# SL_FPGA_Auto_2E.net
KiCad netlist of a schematic drawn in Altium Designer
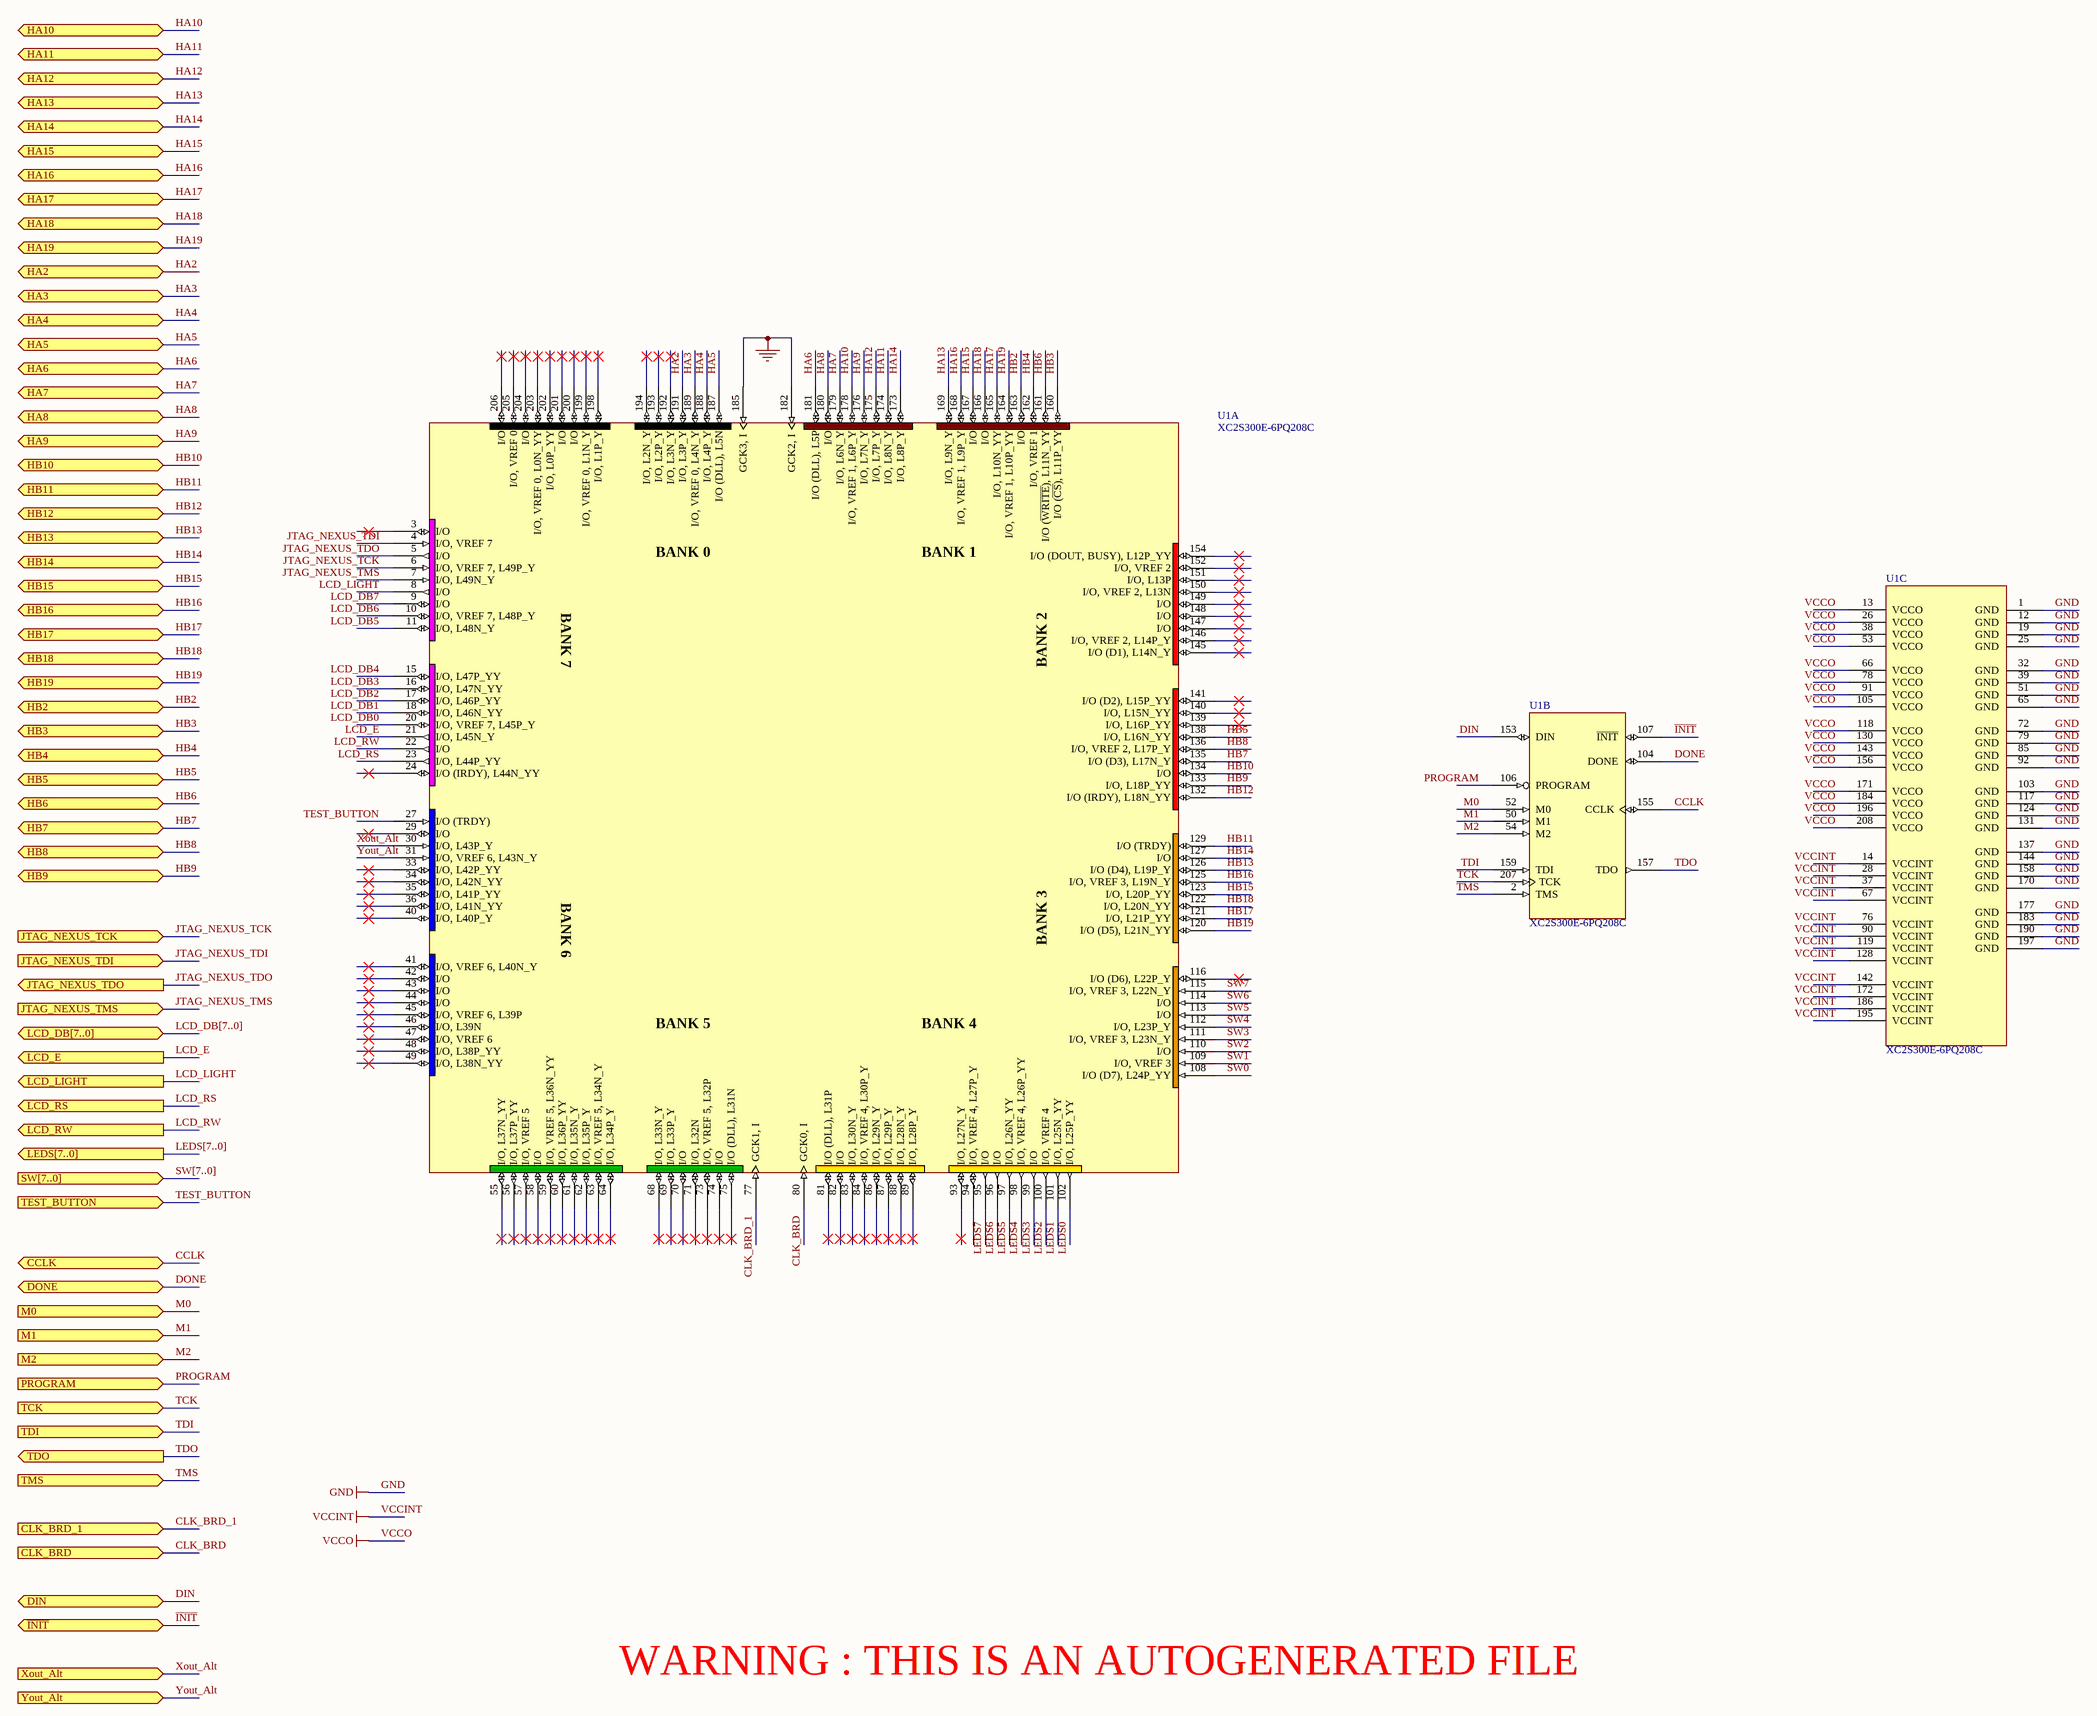
[diagram p0: SL_FPGA_Auto_2E.SchDoc]

(export (version "E")
  (design (tool "Eeschema 10.0.6"))
  (components
    (comp (ref "U1")
      (value "XC2S300E-6PQ208C")
      (footprint "PQ208")
      (description "Spartan-IIE 1.8V FPGA, 208-Pin PQFP, Standard Performance, Commercial Grade")
      (fields (field (name "PUBLISHER") "Altium Limited"))
      (libsource (lib "*") (part "XC2S300E-6PQ208C"))
    )
  )
  (nets
    (net (code "1") (name "/CCLK") (class "Default")
      (node (ref "U1") (pin "155") (pinfunction "CCLK_155") (pintype "bidirectional"))
    )
    (net (code "2") (name "/CLK_BRD") (class "Default")
      (node (ref "U1") (pin "80") (pinfunction "GCK0,_I_80") (pintype "input"))
    )
    (net (code "3") (name "/CLK_BRD_1") (class "Default")
      (node (ref "U1") (pin "77") (pinfunction "GCK1,_I_77") (pintype "input"))
    )
    (net (code "4") (name "/DIN") (class "Default")
      (node (ref "U1") (pin "153") (pinfunction "DIN_153") (pintype "bidirectional"))
    )
    (net (code "5") (name "/DONE") (class "Default")
      (node (ref "U1") (pin "104") (pinfunction "DONE_104") (pintype "bidirectional"))
    )
    (net (code "6") (name "/HA2") (class "Default")
      (node (ref "U1") (pin "191") (pinfunction "I/O,_L3P_Y_191") (pintype "bidirectional"))
    )
    (net (code "7") (name "/HA3") (class "Default")
      (node (ref "U1") (pin "189") (pinfunction "I/O,_VREF_0,_L4N_Y_189") (pintype "bidirectional"))
    )
    (net (code "8") (name "/HA4") (class "Default")
      (node (ref "U1") (pin "188") (pinfunction "I/O,_L4P_Y_188") (pintype "bidirectional"))
    )
    (net (code "9") (name "/HA5") (class "Default")
      (node (ref "U1") (pin "187") (pinfunction "I/O_(DLL),_L5N_187") (pintype "bidirectional"))
    )
    (net (code "10") (name "/HA6") (class "Default")
      (node (ref "U1") (pin "181") (pinfunction "I/O_(DLL),_L5P_181") (pintype "bidirectional"))
    )
    (net (code "11") (name "/HA7") (class "Default")
      (node (ref "U1") (pin "179") (pinfunction "I/O,_L6N_Y_179") (pintype "bidirectional"))
    )
    (net (code "12") (name "/HA8") (class "Default")
      (node (ref "U1") (pin "180") (pinfunction "I/O_180") (pintype "bidirectional"))
    )
    (net (code "13") (name "/HA9") (class "Default")
      (node (ref "U1") (pin "176") (pinfunction "I/O,_L7N_Y_176") (pintype "bidirectional"))
    )
    (net (code "14") (name "/HA10") (class "Default")
      (node (ref "U1") (pin "178") (pinfunction "I/O,_VREF_1,_L6P_Y_178") (pintype "bidirectional"))
    )
    (net (code "15") (name "/HA11") (class "Default")
      (node (ref "U1") (pin "174") (pinfunction "I/O,_L8N_Y_174") (pintype "bidirectional"))
    )
    (net (code "16") (name "/HA12") (class "Default")
      (node (ref "U1") (pin "175") (pinfunction "I/O,_L7P_Y_175") (pintype "bidirectional"))
    )
    (net (code "17") (name "/HA13") (class "Default")
      (node (ref "U1") (pin "169") (pinfunction "I/O,_L9N_Y_169") (pintype "bidirectional"))
    )
    (net (code "18") (name "/HA14") (class "Default")
      (node (ref "U1") (pin "173") (pinfunction "I/O,_L8P_Y_173") (pintype "bidirectional"))
    )
    (net (code "19") (name "/HA15") (class "Default")
      (node (ref "U1") (pin "167") (pinfunction "I/O_167") (pintype "bidirectional"))
    )
    (net (code "20") (name "/HA16") (class "Default")
      (node (ref "U1") (pin "168") (pinfunction "I/O,_VREF_1,_L9P_Y_168") (pintype "bidirectional"))
    )
    (net (code "21") (name "/HA17") (class "Default")
      (node (ref "U1") (pin "165") (pinfunction "I/O,_L10N_YY_165") (pintype "bidirectional"))
    )
    (net (code "22") (name "/HA18") (class "Default")
      (node (ref "U1") (pin "166") (pinfunction "I/O_166") (pintype "bidirectional"))
    )
    (net (code "23") (name "/HA19") (class "Default")
      (node (ref "U1") (pin "164") (pinfunction "I/O,_VREF_1,_L10P_YY_164") (pintype "bidirectional"))
    )
    (net (code "24") (name "/HB2") (class "Default")
      (node (ref "U1") (pin "163") (pinfunction "I/O_163") (pintype "bidirectional"))
    )
    (net (code "25") (name "/HB3") (class "Default")
      (node (ref "U1") (pin "160") (pinfunction "I/O_(~{CS}),_L11P_YY_160") (pintype "bidirectional"))
    )
    (net (code "26") (name "/HB4") (class "Default")
      (node (ref "U1") (pin "162") (pinfunction "I/O,_VREF_1_162") (pintype "bidirectional"))
    )
    (net (code "27") (name "/HB5") (class "Default")
      (node (ref "U1") (pin "138") (pinfunction "I/O,_L16N_YY_138") (pintype "bidirectional"))
    )
    (net (code "28") (name "/HB6") (class "Default")
      (node (ref "U1") (pin "161") (pinfunction "I/O_(~{WRITE}),_L11N_YY_161") (pintype "bidirectional"))
    )
    (net (code "29") (name "/HB7") (class "Default")
      (node (ref "U1") (pin "135") (pinfunction "I/O_(D3),_L17N_Y_135") (pintype "bidirectional"))
    )
    (net (code "30") (name "/HB8") (class "Default")
      (node (ref "U1") (pin "136") (pinfunction "I/O,_VREF_2,_L17P_Y_136") (pintype "bidirectional"))
    )
    (net (code "31") (name "/HB9") (class "Default")
      (node (ref "U1") (pin "133") (pinfunction "I/O,_L18P_YY_133") (pintype "bidirectional"))
    )
    (net (code "32") (name "/HB10") (class "Default")
      (node (ref "U1") (pin "134") (pinfunction "I/O_134") (pintype "bidirectional"))
    )
    (net (code "33") (name "/HB11") (class "Default")
      (node (ref "U1") (pin "129") (pinfunction "I/O_(TRDY)_129") (pintype "bidirectional"))
    )
    (net (code "34") (name "/HB12") (class "Default")
      (node (ref "U1") (pin "132") (pinfunction "I/O_(IRDY),_L18N_YY_132") (pintype "bidirectional"))
    )
    (net (code "35") (name "/HB13") (class "Default")
      (node (ref "U1") (pin "126") (pinfunction "I/O_(D4),_L19P_Y_126") (pintype "bidirectional"))
    )
    (net (code "36") (name "/HB14") (class "Default")
      (node (ref "U1") (pin "127") (pinfunction "I/O_127") (pintype "bidirectional"))
    )
    (net (code "37") (name "/HB15") (class "Default")
      (node (ref "U1") (pin "123") (pinfunction "I/O,_L20P_YY_123") (pintype "bidirectional"))
    )
    (net (code "38") (name "/HB16") (class "Default")
      (node (ref "U1") (pin "125") (pinfunction "I/O,_VREF_3,_L19N_Y_125") (pintype "bidirectional"))
    )
    (net (code "39") (name "/HB17") (class "Default")
      (node (ref "U1") (pin "121") (pinfunction "I/O,_L21P_YY_121") (pintype "bidirectional"))
    )
    (net (code "40") (name "/HB18") (class "Default")
      (node (ref "U1") (pin "122") (pinfunction "I/O,_L20N_YY_122") (pintype "bidirectional"))
    )
    (net (code "41") (name "/HB19") (class "Default")
      (node (ref "U1") (pin "120") (pinfunction "I/O_(D5),_L21N_YY_120") (pintype "bidirectional"))
    )
    (net (code "42") (name "/JTAG_NEXUS_TCK") (class "Default")
      (node (ref "U1") (pin "6") (pinfunction "I/O,_VREF_7,_L49P_Y_6") (pintype "input"))
    )
    (net (code "43") (name "/JTAG_NEXUS_TDI") (class "Default")
      (node (ref "U1") (pin "4") (pinfunction "I/O,_VREF_7_4") (pintype "input"))
    )
    (net (code "44") (name "/JTAG_NEXUS_TDO") (class "Default")
      (node (ref "U1") (pin "5") (pinfunction "I/O_5") (pintype "output"))
    )
    (net (code "45") (name "/JTAG_NEXUS_TMS") (class "Default")
      (node (ref "U1") (pin "7") (pinfunction "I/O,_L49N_Y_7") (pintype "input"))
    )
    (net (code "46") (name "/LCD_DB0") (class "Default")
      (node (ref "U1") (pin "20") (pinfunction "I/O,_VREF_7,_L45P_Y_20") (pintype "bidirectional"))
    )
    (net (code "47") (name "/LCD_DB1") (class "Default")
      (node (ref "U1") (pin "18") (pinfunction "I/O,_L46N_YY_18") (pintype "bidirectional"))
    )
    (net (code "48") (name "/LCD_DB2") (class "Default")
      (node (ref "U1") (pin "17") (pinfunction "I/O,_L46P_YY_17") (pintype "bidirectional"))
    )
    (net (code "49") (name "/LCD_DB3") (class "Default")
      (node (ref "U1") (pin "16") (pinfunction "I/O,_L47N_YY_16") (pintype "bidirectional"))
    )
    (net (code "50") (name "/LCD_DB4") (class "Default")
      (node (ref "U1") (pin "15") (pinfunction "I/O,_L47P_YY_15") (pintype "bidirectional"))
    )
    (net (code "51") (name "/LCD_DB5") (class "Default")
      (node (ref "U1") (pin "11") (pinfunction "I/O,_L48N_Y_11") (pintype "bidirectional"))
    )
    (net (code "52") (name "/LCD_DB6") (class "Default")
      (node (ref "U1") (pin "10") (pinfunction "I/O,_VREF_7,_L48P_Y_10") (pintype "bidirectional"))
    )
    (net (code "53") (name "/LCD_DB7") (class "Default")
      (node (ref "U1") (pin "9") (pinfunction "I/O_9") (pintype "bidirectional"))
    )
    (net (code "55") (name "/LCD_E") (class "Default")
      (node (ref "U1") (pin "21") (pinfunction "I/O,_L45N_Y_21") (pintype "output"))
    )
    (net (code "56") (name "/LCD_LIGHT") (class "Default")
      (node (ref "U1") (pin "8") (pinfunction "I/O_8") (pintype "output"))
    )
    (net (code "57") (name "/LCD_RS") (class "Default")
      (node (ref "U1") (pin "23") (pinfunction "I/O,_L44P_YY_23") (pintype "output"))
    )
    (net (code "58") (name "/LCD_RW") (class "Default")
      (node (ref "U1") (pin "22") (pinfunction "I/O_22") (pintype "output"))
    )
    (net (code "59") (name "/LEDS0") (class "Default")
      (node (ref "U1") (pin "102") (pinfunction "I/O,_L25P_YY_102") (pintype "output"))
    )
    (net (code "60") (name "/LEDS1") (class "Default")
      (node (ref "U1") (pin "101") (pinfunction "I/O,_L25N_YY_101") (pintype "output"))
    )
    (net (code "61") (name "/LEDS2") (class "Default")
      (node (ref "U1") (pin "100") (pinfunction "I/O,_VREF_4_100") (pintype "output"))
    )
    (net (code "62") (name "/LEDS3") (class "Default")
      (node (ref "U1") (pin "99") (pinfunction "I/O_99") (pintype "output"))
    )
    (net (code "63") (name "/LEDS4") (class "Default")
      (node (ref "U1") (pin "98") (pinfunction "I/O,_VREF_4,_L26P_YY_98") (pintype "output"))
    )
    (net (code "64") (name "/LEDS5") (class "Default")
      (node (ref "U1") (pin "97") (pinfunction "I/O,_L26N_YY_97") (pintype "output"))
    )
    (net (code "65") (name "/LEDS6") (class "Default")
      (node (ref "U1") (pin "96") (pinfunction "I/O_96") (pintype "output"))
    )
    (net (code "66") (name "/LEDS7") (class "Default")
      (node (ref "U1") (pin "95") (pinfunction "I/O_95") (pintype "output"))
    )
    (net (code "68") (name "/M0") (class "Default")
      (node (ref "U1") (pin "52") (pinfunction "M0_52") (pintype "input"))
    )
    (net (code "69") (name "/M1") (class "Default")
      (node (ref "U1") (pin "50") (pinfunction "M1_50") (pintype "input"))
    )
    (net (code "70") (name "/M2") (class "Default")
      (node (ref "U1") (pin "54") (pinfunction "M2_54") (pintype "input"))
    )
    (net (code "71") (name "/PROGRAM") (class "Default")
      (node (ref "U1") (pin "106") (pinfunction "PROGRAM_106") (pintype "input"))
    )
    (net (code "72") (name "/SW0") (class "Default")
      (node (ref "U1") (pin "108") (pinfunction "I/O_(D7),_L24P_YY_108") (pintype "input"))
    )
    (net (code "73") (name "/SW1") (class "Default")
      (node (ref "U1") (pin "109") (pinfunction "I/O,_VREF_3_109") (pintype "input"))
    )
    (net (code "74") (name "/SW2") (class "Default")
      (node (ref "U1") (pin "110") (pinfunction "I/O_110") (pintype "input"))
    )
    (net (code "75") (name "/SW3") (class "Default")
      (node (ref "U1") (pin "111") (pinfunction "I/O,_VREF_3,_L23N_Y_111") (pintype "input"))
    )
    (net (code "76") (name "/SW4") (class "Default")
      (node (ref "U1") (pin "112") (pinfunction "I/O,_L23P_Y_112") (pintype "input"))
    )
    (net (code "77") (name "/SW5") (class "Default")
      (node (ref "U1") (pin "113") (pinfunction "I/O_113") (pintype "input"))
    )
    (net (code "78") (name "/SW6") (class "Default")
      (node (ref "U1") (pin "114") (pinfunction "I/O_114") (pintype "input"))
    )
    (net (code "79") (name "/SW7") (class "Default")
      (node (ref "U1") (pin "115") (pinfunction "I/O,_VREF_3,_L22N_Y_115") (pintype "input"))
    )
    (net (code "81") (name "/TCK") (class "Default")
      (node (ref "U1") (pin "207") (pinfunction "TCK_207") (pintype "input"))
    )
    (net (code "82") (name "/TDI") (class "Default")
      (node (ref "U1") (pin "159") (pinfunction "TDI_159") (pintype "input"))
    )
    (net (code "83") (name "/TDO") (class "Default")
      (node (ref "U1") (pin "157") (pinfunction "TDO_157") (pintype "output"))
    )
    (net (code "84") (name "/TEST_BUTTON") (class "Default")
      (node (ref "U1") (pin "27") (pinfunction "I/O_(TRDY)_27") (pintype "input"))
    )
    (net (code "85") (name "/TMS") (class "Default")
      (node (ref "U1") (pin "2") (pinfunction "TMS_2") (pintype "input"))
    )
    (net (code "86") (name "/Xout_Alt") (class "Default")
      (node (ref "U1") (pin "30") (pinfunction "I/O,_L43P_Y_30") (pintype "input"))
    )
    (net (code "87") (name "/Yout_Alt") (class "Default")
      (node (ref "U1") (pin "31") (pinfunction "I/O,_VREF_6,_L43N_Y_31") (pintype "input"))
    )
    (net (code "88") (name "/~{INIT}") (class "Default")
      (node (ref "U1") (pin "107") (pinfunction "~{INIT}_107") (pintype "bidirectional"))
    )
    (net (code "89") (name "GND") (class "Default")
      (node (ref "U1") (pin "1") (pinfunction "GND_1") (pintype "power_in"))
      (node (ref "U1") (pin "103") (pinfunction "GND_103") (pintype "power_in"))
      (node (ref "U1") (pin "117") (pinfunction "GND_117") (pintype "power_in"))
      (node (ref "U1") (pin "12") (pinfunction "GND_12") (pintype "power_in"))
      (node (ref "U1") (pin "124") (pinfunction "GND_124") (pintype "power_in"))
      (node (ref "U1") (pin "131") (pinfunction "GND_131") (pintype "power_in"))
      (node (ref "U1") (pin "137") (pinfunction "GND_137") (pintype "power_in"))
      (node (ref "U1") (pin "144") (pinfunction "GND_144") (pintype "power_in"))
      (node (ref "U1") (pin "158") (pinfunction "GND_158") (pintype "power_in"))
      (node (ref "U1") (pin "170") (pinfunction "GND_170") (pintype "power_in"))
      (node (ref "U1") (pin "177") (pinfunction "GND_177") (pintype "power_in"))
      (node (ref "U1") (pin "182") (pinfunction "GCK2,_I_182") (pintype "input"))
      (node (ref "U1") (pin "183") (pinfunction "GND_183") (pintype "power_in"))
      (node (ref "U1") (pin "185") (pinfunction "GCK3,_I_185") (pintype "input"))
      (node (ref "U1") (pin "19") (pinfunction "GND_19") (pintype "power_in"))
      (node (ref "U1") (pin "190") (pinfunction "GND_190") (pintype "power_in"))
      (node (ref "U1") (pin "197") (pinfunction "GND_197") (pintype "power_in"))
      (node (ref "U1") (pin "25") (pinfunction "GND_25") (pintype "power_in"))
      (node (ref "U1") (pin "32") (pinfunction "GND_32") (pintype "power_in"))
      (node (ref "U1") (pin "39") (pinfunction "GND_39") (pintype "power_in"))
      (node (ref "U1") (pin "51") (pinfunction "GND_51") (pintype "power_in"))
      (node (ref "U1") (pin "65") (pinfunction "GND_65") (pintype "power_in"))
      (node (ref "U1") (pin "72") (pinfunction "GND_72") (pintype "power_in"))
      (node (ref "U1") (pin "79") (pinfunction "GND_79") (pintype "power_in"))
      (node (ref "U1") (pin "85") (pinfunction "GND_85") (pintype "power_in"))
      (node (ref "U1") (pin "92") (pinfunction "GND_92") (pintype "power_in"))
    )
    (net (code "90") (name "VCCINT") (class "Default")
      (node (ref "U1") (pin "119") (pinfunction "VCCINT_119") (pintype "power_in"))
      (node (ref "U1") (pin "128") (pinfunction "VCCINT_128") (pintype "power_in"))
      (node (ref "U1") (pin "14") (pinfunction "VCCINT_14") (pintype "power_in"))
      (node (ref "U1") (pin "142") (pinfunction "VCCINT_142") (pintype "power_in"))
      (node (ref "U1") (pin "172") (pinfunction "VCCINT_172") (pintype "power_in"))
      (node (ref "U1") (pin "186") (pinfunction "VCCINT_186") (pintype "power_in"))
      (node (ref "U1") (pin "195") (pinfunction "VCCINT_195") (pintype "power_in"))
      (node (ref "U1") (pin "28") (pinfunction "VCCINT_28") (pintype "power_in"))
      (node (ref "U1") (pin "37") (pinfunction "VCCINT_37") (pintype "power_in"))
      (node (ref "U1") (pin "67") (pinfunction "VCCINT_67") (pintype "power_in"))
      (node (ref "U1") (pin "76") (pinfunction "VCCINT_76") (pintype "power_in"))
      (node (ref "U1") (pin "90") (pinfunction "VCCINT_90") (pintype "power_in"))
    )
    (net (code "91") (name "VCCO") (class "Default")
      (node (ref "U1") (pin "105") (pinfunction "VCCO_105") (pintype "power_in"))
      (node (ref "U1") (pin "118") (pinfunction "VCCO_118") (pintype "power_in"))
      (node (ref "U1") (pin "13") (pinfunction "VCCO_13") (pintype "power_in"))
      (node (ref "U1") (pin "130") (pinfunction "VCCO_130") (pintype "power_in"))
      (node (ref "U1") (pin "143") (pinfunction "VCCO_143") (pintype "power_in"))
      (node (ref "U1") (pin "156") (pinfunction "VCCO_156") (pintype "power_in"))
      (node (ref "U1") (pin "171") (pinfunction "VCCO_171") (pintype "power_in"))
      (node (ref "U1") (pin "184") (pinfunction "VCCO_184") (pintype "power_in"))
      (node (ref "U1") (pin "196") (pinfunction "VCCO_196") (pintype "power_in"))
      (node (ref "U1") (pin "208") (pinfunction "VCCO_208") (pintype "power_in"))
      (node (ref "U1") (pin "26") (pinfunction "VCCO_26") (pintype "power_in"))
      (node (ref "U1") (pin "38") (pinfunction "VCCO_38") (pintype "power_in"))
      (node (ref "U1") (pin "53") (pinfunction "VCCO_53") (pintype "power_in"))
      (node (ref "U1") (pin "66") (pinfunction "VCCO_66") (pintype "power_in"))
      (node (ref "U1") (pin "78") (pinfunction "VCCO_78") (pintype "power_in"))
      (node (ref "U1") (pin "91") (pinfunction "VCCO_91") (pintype "power_in"))
    )
    (net (code "92") (name "unconnected-(U1A-I{slash}O,_L0P_YY-Pad202)") (class "Default")
      (node (ref "U1") (pin "202") (pinfunction "I/O,_L0P_YY_202") (pintype "bidirectional"))
    )
    (net (code "93") (name "unconnected-(U1A-I{slash}O,_L1P_Y-Pad198)") (class "Default")
      (node (ref "U1") (pin "198") (pinfunction "I/O,_L1P_Y_198") (pintype "bidirectional"))
    )
    (net (code "94") (name "unconnected-(U1A-I{slash}O,_L2N_Y-Pad194)") (class "Default")
      (node (ref "U1") (pin "194") (pinfunction "I/O,_L2N_Y_194") (pintype "bidirectional"))
    )
    (net (code "95") (name "unconnected-(U1A-I{slash}O,_L2P_Y-Pad193)") (class "Default")
      (node (ref "U1") (pin "193") (pinfunction "I/O,_L2P_Y_193") (pintype "bidirectional"))
    )
    (net (code "96") (name "unconnected-(U1A-I{slash}O,_L3N_Y-Pad192)") (class "Default")
      (node (ref "U1") (pin "192") (pinfunction "I/O,_L3N_Y_192") (pintype "bidirectional"))
    )
    (net (code "97") (name "unconnected-(U1A-I{slash}O,_L13P-Pad151)") (class "Default")
      (node (ref "U1") (pin "151") (pinfunction "I/O,_L13P_151") (pintype "bidirectional"))
    )
    (net (code "98") (name "unconnected-(U1A-I{slash}O,_L15N_YY-Pad140)") (class "Default")
      (node (ref "U1") (pin "140") (pinfunction "I/O,_L15N_YY_140") (pintype "bidirectional"))
    )
    (net (code "99") (name "unconnected-(U1A-I{slash}O,_L16P_YY-Pad139)") (class "Default")
      (node (ref "U1") (pin "139") (pinfunction "I/O,_L16P_YY_139") (pintype "bidirectional"))
    )
    (net (code "100") (name "unconnected-(U1A-I{slash}O,_L27N_Y-Pad93)") (class "Default")
      (node (ref "U1") (pin "93") (pinfunction "I/O,_L27N_Y_93") (pintype "bidirectional"))
    )
    (net (code "101") (name "unconnected-(U1A-I{slash}O,_L28N_Y-Pad88)") (class "Default")
      (node (ref "U1") (pin "88") (pinfunction "I/O,_L28N_Y_88") (pintype "bidirectional"))
    )
    (net (code "102") (name "unconnected-(U1A-I{slash}O,_L28P_Y-Pad89)") (class "Default")
      (node (ref "U1") (pin "89") (pinfunction "I/O,_L28P_Y_89") (pintype "bidirectional"))
    )
    (net (code "103") (name "unconnected-(U1A-I{slash}O,_L29N_Y-Pad86)") (class "Default")
      (node (ref "U1") (pin "86") (pinfunction "I/O,_L29N_Y_86") (pintype "bidirectional"))
    )
    (net (code "104") (name "unconnected-(U1A-I{slash}O,_L29P_Y-Pad87)") (class "Default")
      (node (ref "U1") (pin "87") (pinfunction "I/O,_L29P_Y_87") (pintype "bidirectional"))
    )
    (net (code "105") (name "unconnected-(U1A-I{slash}O,_L30N_Y-Pad83)") (class "Default")
      (node (ref "U1") (pin "83") (pinfunction "I/O,_L30N_Y_83") (pintype "bidirectional"))
    )
    (net (code "106") (name "unconnected-(U1A-I{slash}O,_L32N-Pad71)") (class "Default")
      (node (ref "U1") (pin "71") (pinfunction "I/O,_L32N_71") (pintype "bidirectional"))
    )
    (net (code "107") (name "unconnected-(U1A-I{slash}O,_L33N_Y-Pad68)") (class "Default")
      (node (ref "U1") (pin "68") (pinfunction "I/O,_L33N_Y_68") (pintype "bidirectional"))
    )
    (net (code "108") (name "unconnected-(U1A-I{slash}O,_L33P_Y-Pad69)") (class "Default")
      (node (ref "U1") (pin "69") (pinfunction "I/O,_L33P_Y_69") (pintype "bidirectional"))
    )
    (net (code "109") (name "unconnected-(U1A-I{slash}O,_L34P_Y-Pad64)") (class "Default")
      (node (ref "U1") (pin "64") (pinfunction "I/O,_L34P_Y_64") (pintype "bidirectional"))
    )
    (net (code "110") (name "unconnected-(U1A-I{slash}O,_L35N_Y-Pad61)") (class "Default")
      (node (ref "U1") (pin "61") (pinfunction "I/O,_L35N_Y_61") (pintype "bidirectional"))
    )
    (net (code "111") (name "unconnected-(U1A-I{slash}O,_L35P_Y-Pad62)") (class "Default")
      (node (ref "U1") (pin "62") (pinfunction "I/O,_L35P_Y_62") (pintype "bidirectional"))
    )
    (net (code "112") (name "unconnected-(U1A-I{slash}O,_L36P_YY-Pad60)") (class "Default")
      (node (ref "U1") (pin "60") (pinfunction "I/O,_L36P_YY_60") (pintype "bidirectional"))
    )
    (net (code "113") (name "unconnected-(U1A-I{slash}O,_L37N_YY-Pad55)") (class "Default")
      (node (ref "U1") (pin "55") (pinfunction "I/O,_L37N_YY_55") (pintype "bidirectional"))
    )
    (net (code "114") (name "unconnected-(U1A-I{slash}O,_L37P_YY-Pad56)") (class "Default")
      (node (ref "U1") (pin "56") (pinfunction "I/O,_L37P_YY_56") (pintype "bidirectional"))
    )
    (net (code "115") (name "unconnected-(U1A-I{slash}O,_L38N_YY-Pad49)") (class "Default")
      (node (ref "U1") (pin "49") (pinfunction "I/O,_L38N_YY_49") (pintype "bidirectional"))
    )
    (net (code "116") (name "unconnected-(U1A-I{slash}O,_L38P_YY-Pad48)") (class "Default")
      (node (ref "U1") (pin "48") (pinfunction "I/O,_L38P_YY_48") (pintype "bidirectional"))
    )
    (net (code "117") (name "unconnected-(U1A-I{slash}O,_L39N-Pad46)") (class "Default")
      (node (ref "U1") (pin "46") (pinfunction "I/O,_L39N_46") (pintype "bidirectional"))
    )
    (net (code "118") (name "unconnected-(U1A-I{slash}O,_L40P_Y-Pad40)") (class "Default")
      (node (ref "U1") (pin "40") (pinfunction "I/O,_L40P_Y_40") (pintype "bidirectional"))
    )
    (net (code "119") (name "unconnected-(U1A-I{slash}O,_L41N_YY-Pad36)") (class "Default")
      (node (ref "U1") (pin "36") (pinfunction "I/O,_L41N_YY_36") (pintype "bidirectional"))
    )
    (net (code "120") (name "unconnected-(U1A-I{slash}O,_L41P_YY-Pad35)") (class "Default")
      (node (ref "U1") (pin "35") (pinfunction "I/O,_L41P_YY_35") (pintype "bidirectional"))
    )
    (net (code "121") (name "unconnected-(U1A-I{slash}O,_L42N_YY-Pad34)") (class "Default")
      (node (ref "U1") (pin "34") (pinfunction "I/O,_L42N_YY_34") (pintype "bidirectional"))
    )
    (net (code "122") (name "unconnected-(U1A-I{slash}O,_L42P_YY-Pad33)") (class "Default")
      (node (ref "U1") (pin "33") (pinfunction "I/O,_L42P_YY_33") (pintype "bidirectional"))
    )
    (net (code "123") (name "unconnected-(U1A-I{slash}O,_VREF_0,_L0N_YY-Pad203)") (class "Default")
      (node (ref "U1") (pin "203") (pinfunction "I/O,_VREF_0,_L0N_YY_203") (pintype "bidirectional"))
    )
    (net (code "124") (name "unconnected-(U1A-I{slash}O,_VREF_0,_L1N_Y-Pad199)") (class "Default")
      (node (ref "U1") (pin "199") (pinfunction "I/O,_VREF_0,_L1N_Y_199") (pintype "bidirectional"))
    )
    (net (code "125") (name "unconnected-(U1A-I{slash}O,_VREF_0-Pad205)") (class "Default")
      (node (ref "U1") (pin "205") (pinfunction "I/O,_VREF_0_205") (pintype "bidirectional"))
    )
    (net (code "126") (name "unconnected-(U1A-I{slash}O,_VREF_2,_L13N-Pad150)") (class "Default")
      (node (ref "U1") (pin "150") (pinfunction "I/O,_VREF_2,_L13N_150") (pintype "bidirectional"))
    )
    (net (code "127") (name "unconnected-(U1A-I{slash}O,_VREF_2,_L14P_Y-Pad146)") (class "Default")
      (node (ref "U1") (pin "146") (pinfunction "I/O,_VREF_2,_L14P_Y_146") (pintype "bidirectional"))
    )
    (net (code "128") (name "unconnected-(U1A-I{slash}O,_VREF_2-Pad152)") (class "Default")
      (node (ref "U1") (pin "152") (pinfunction "I/O,_VREF_2_152") (pintype "bidirectional"))
    )
    (net (code "129") (name "unconnected-(U1A-I{slash}O,_VREF_4,_L27P_Y-Pad94)") (class "Default")
      (node (ref "U1") (pin "94") (pinfunction "I/O,_VREF_4,_L27P_Y_94") (pintype "bidirectional"))
    )
    (net (code "130") (name "unconnected-(U1A-I{slash}O,_VREF_4,_L30P_Y-Pad84)") (class "Default")
      (node (ref "U1") (pin "84") (pinfunction "I/O,_VREF_4,_L30P_Y_84") (pintype "bidirectional"))
    )
    (net (code "131") (name "unconnected-(U1A-I{slash}O,_VREF_5,_L32P-Pad73)") (class "Default")
      (node (ref "U1") (pin "73") (pinfunction "I/O,_VREF_5,_L32P_73") (pintype "bidirectional"))
    )
    (net (code "132") (name "unconnected-(U1A-I{slash}O,_VREF_5,_L34N_Y-Pad63)") (class "Default")
      (node (ref "U1") (pin "63") (pinfunction "I/O,_VREF_5,_L34N_Y_63") (pintype "bidirectional"))
    )
    (net (code "133") (name "unconnected-(U1A-I{slash}O,_VREF_5,_L36N_YY-Pad59)") (class "Default")
      (node (ref "U1") (pin "59") (pinfunction "I/O,_VREF_5,_L36N_YY_59") (pintype "bidirectional"))
    )
    (net (code "134") (name "unconnected-(U1A-I{slash}O,_VREF_5-Pad57)") (class "Default")
      (node (ref "U1") (pin "57") (pinfunction "I/O,_VREF_5_57") (pintype "bidirectional"))
    )
    (net (code "135") (name "unconnected-(U1A-I{slash}O,_VREF_6,_L39P-Pad45)") (class "Default")
      (node (ref "U1") (pin "45") (pinfunction "I/O,_VREF_6,_L39P_45") (pintype "bidirectional"))
    )
    (net (code "136") (name "unconnected-(U1A-I{slash}O,_VREF_6,_L40N_Y-Pad41)") (class "Default")
      (node (ref "U1") (pin "41") (pinfunction "I/O,_VREF_6,_L40N_Y_41") (pintype "bidirectional"))
    )
    (net (code "137") (name "unconnected-(U1A-I{slash}O,_VREF_6-Pad47)") (class "Default")
      (node (ref "U1") (pin "47") (pinfunction "I/O,_VREF_6_47") (pintype "bidirectional"))
    )
    (net (code "138") (name "unconnected-(U1A-I{slash}O-Pad3)") (class "Default")
      (node (ref "U1") (pin "3") (pinfunction "I/O_3") (pintype "bidirectional"))
    )
    (net (code "139") (name "unconnected-(U1A-I{slash}O-Pad29)") (class "Default")
      (node (ref "U1") (pin "29") (pinfunction "I/O_29") (pintype "bidirectional"))
    )
    (net (code "140") (name "unconnected-(U1A-I{slash}O-Pad42)") (class "Default")
      (node (ref "U1") (pin "42") (pinfunction "I/O_42") (pintype "bidirectional"))
    )
    (net (code "141") (name "unconnected-(U1A-I{slash}O-Pad43)") (class "Default")
      (node (ref "U1") (pin "43") (pinfunction "I/O_43") (pintype "bidirectional"))
    )
    (net (code "142") (name "unconnected-(U1A-I{slash}O-Pad44)") (class "Default")
      (node (ref "U1") (pin "44") (pinfunction "I/O_44") (pintype "bidirectional"))
    )
    (net (code "143") (name "unconnected-(U1A-I{slash}O-Pad58)") (class "Default")
      (node (ref "U1") (pin "58") (pinfunction "I/O_58") (pintype "bidirectional"))
    )
    (net (code "144") (name "unconnected-(U1A-I{slash}O-Pad70)") (class "Default")
      (node (ref "U1") (pin "70") (pinfunction "I/O_70") (pintype "bidirectional"))
    )
    (net (code "145") (name "unconnected-(U1A-I{slash}O-Pad74)") (class "Default")
      (node (ref "U1") (pin "74") (pinfunction "I/O_74") (pintype "bidirectional"))
    )
    (net (code "146") (name "unconnected-(U1A-I{slash}O-Pad82)") (class "Default")
      (node (ref "U1") (pin "82") (pinfunction "I/O_82") (pintype "bidirectional"))
    )
    (net (code "147") (name "unconnected-(U1A-I{slash}O-Pad147)") (class "Default")
      (node (ref "U1") (pin "147") (pinfunction "I/O_147") (pintype "bidirectional"))
    )
    (net (code "148") (name "unconnected-(U1A-I{slash}O-Pad148)") (class "Default")
      (node (ref "U1") (pin "148") (pinfunction "I/O_148") (pintype "bidirectional"))
    )
    (net (code "149") (name "unconnected-(U1A-I{slash}O-Pad149)") (class "Default")
      (node (ref "U1") (pin "149") (pinfunction "I/O_149") (pintype "bidirectional"))
    )
    (net (code "150") (name "unconnected-(U1A-I{slash}O-Pad200)") (class "Default")
      (node (ref "U1") (pin "200") (pinfunction "I/O_200") (pintype "bidirectional"))
    )
    (net (code "151") (name "unconnected-(U1A-I{slash}O-Pad201)") (class "Default")
      (node (ref "U1") (pin "201") (pinfunction "I/O_201") (pintype "bidirectional"))
    )
    (net (code "152") (name "unconnected-(U1A-I{slash}O-Pad204)") (class "Default")
      (node (ref "U1") (pin "204") (pinfunction "I/O_204") (pintype "bidirectional"))
    )
    (net (code "153") (name "unconnected-(U1A-I{slash}O-Pad206)") (class "Default")
      (node (ref "U1") (pin "206") (pinfunction "I/O_206") (pintype "bidirectional"))
    )
    (net (code "154") (name "unconnected-(U1A-I{slash}O_(D1),_L14N_Y-Pad145)") (class "Default")
      (node (ref "U1") (pin "145") (pinfunction "I/O_(D1),_L14N_Y_145") (pintype "bidirectional"))
    )
    (net (code "155") (name "unconnected-(U1A-I{slash}O_(D2),_L15P_YY-Pad141)") (class "Default")
      (node (ref "U1") (pin "141") (pinfunction "I/O_(D2),_L15P_YY_141") (pintype "bidirectional"))
    )
    (net (code "156") (name "unconnected-(U1A-I{slash}O_(D6),_L22P_Y-Pad116)") (class "Default")
      (node (ref "U1") (pin "116") (pinfunction "I/O_(D6),_L22P_Y_116") (pintype "bidirectional"))
    )
    (net (code "157") (name "unconnected-(U1A-I{slash}O_(DLL),_L31N-Pad75)") (class "Default")
      (node (ref "U1") (pin "75") (pinfunction "I/O_(DLL),_L31N_75") (pintype "bidirectional"))
    )
    (net (code "158") (name "unconnected-(U1A-I{slash}O_(DLL),_L31P-Pad81)") (class "Default")
      (node (ref "U1") (pin "81") (pinfunction "I/O_(DLL),_L31P_81") (pintype "bidirectional"))
    )
    (net (code "159") (name "unconnected-(U1A-I{slash}O_(DOUT,_BUSY),_L12P_YY-Pad154)") (class "Default")
      (node (ref "U1") (pin "154") (pinfunction "I/O_(DOUT,_BUSY),_L12P_YY_154") (pintype "bidirectional"))
    )
    (net (code "160") (name "unconnected-(U1A-I{slash}O_(IRDY),_L44N_YY-Pad24)") (class "Default")
      (node (ref "U1") (pin "24") (pinfunction "I/O_(IRDY),_L44N_YY_24") (pintype "bidirectional"))
    )
  )
)
